# Industrial-Controller_3_3V_Domain.net
KiCad netlist of a schematic drawn in Altium Designer
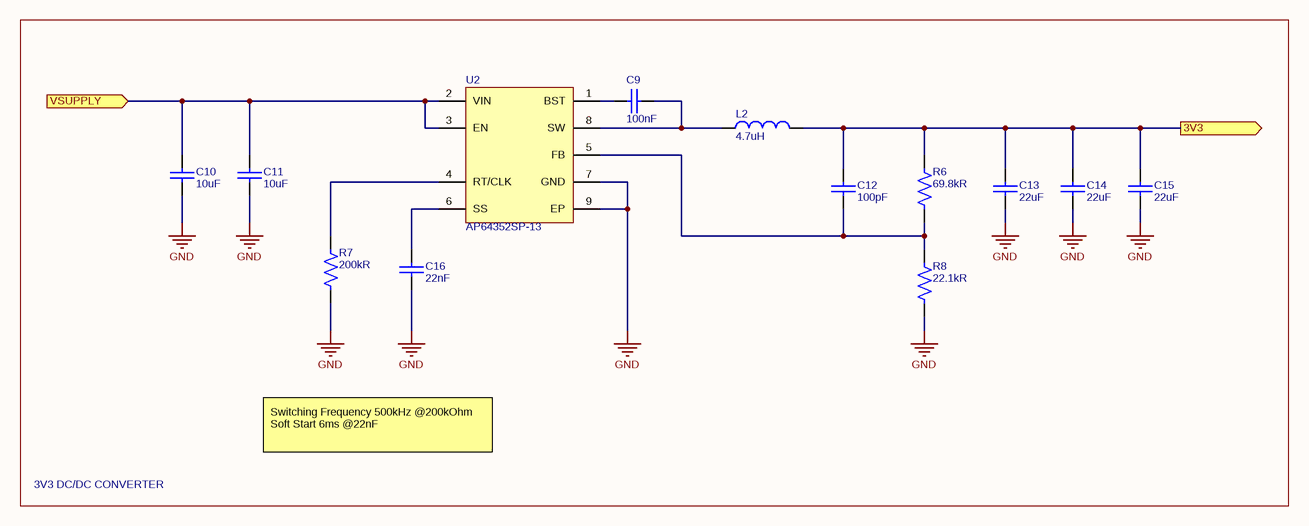
[diagram p0: Industrial-Controller_3.3V_Domain.SchDoc]

(export (version "E")
  (design (tool "Eeschema 10.0.6"))
  (components
    (comp (ref "C9")
      (value "100nF")
      (footprint "CAP_0603")
      (description "CAP CER 0.1UF 50V X7R 0603")
      (fields (field (name "TOLERANCE") "10%"))
      (libsource (lib "Door_Controller_Single") (part "CL10B104KB8NNNL"))
    )
    (comp (ref "C10")
      (value "10uF")
      (footprint "CAP_1210")
      (description "CAP CER 10UF 50V X7R 1210")
      (fields (field (name "TOLERANCE") "10%"))
      (libsource (lib "Door_Controller_Single") (part "CL32B106KBJNNWE"))
    )
    (comp (ref "C11")
      (value "10uF")
      (footprint "CAP_1210")
      (description "CAP CER 10UF 50V X7R 1210")
      (fields (field (name "TOLERANCE") "10%"))
      (libsource (lib "Door_Controller_Single") (part "CL32B106KBJNNWE"))
    )
    (comp (ref "C12")
      (value "100pF")
      (footprint "CAP_0603")
      (description "CAP CER 100PF 50V X7R 0603")
      (fields (field (name "TOLERANCE") "10%"))
      (libsource (lib "Door_Controller_Single") (part "CL10B101KB8NFNC"))
    )
    (comp (ref "C13")
      (value "22uF")
      (footprint "CAP_1210")
      (description "CAP CER 22UF 25V X7R 1210")
      (fields (field (name "TOLERANCE") "10%"))
      (libsource (lib "Door_Controller_Single") (part "CL32B226KAJNNNE"))
    )
    (comp (ref "C14")
      (value "22uF")
      (footprint "CAP_1210")
      (description "CAP CER 22UF 25V X7R 1210")
      (fields (field (name "TOLERANCE") "10%"))
      (libsource (lib "Door_Controller_Single") (part "CL32B226KAJNNNE"))
    )
    (comp (ref "C15")
      (value "22uF")
      (footprint "CAP_1210")
      (description "CAP CER 22UF 25V X7R 1210")
      (fields (field (name "TOLERANCE") "10%"))
      (libsource (lib "Door_Controller_Single") (part "CL32B226KAJNNNE"))
    )
    (comp (ref "C16")
      (value "22nF")
      (footprint "CAP_0603")
      (description "CAP CER 0.022UF 50V X7R 0603")
      (fields (field (name "TOLERANCE") "10%"))
      (libsource (lib "Door_Controller_Single") (part "CL10B223KB8WPNC"))
    )
    (comp (ref "L2")
      (value "4.7uH")
      (footprint "SRU1048")
      (description "FIXED IND 4.7UH 5.5A 9.5MOHM SMD")
      (fields (field (name "TOLERANCE") "30%"))
      (libsource (lib "Door_Controller_Single") (part "SRU1048-4R7Y"))
    )
    (comp (ref "R6")
      (value "69.8kR")
      (footprint "RES_0603")
      (description "RES 69.8K OHM 1% 1/10W 0603")
      (fields (field (name "TOLERANCE") "1%"))
      (libsource (lib "Door_Controller_Single") (part "RC0603FR-0769K8L"))
    )
    (comp (ref "R7")
      (value "200kR")
      (footprint "RES_0603")
      (description "RES 200K OHM 1% 1/10W 0603")
      (fields (field (name "TOLERANCE") "1%"))
      (libsource (lib "Door_Controller_Single") (part "RC0603FR-07200KL"))
    )
    (comp (ref "R8")
      (value "22.1kR")
      (footprint "RES_0603")
      (description "RES 22.1K OHM 1% 1/10W 0603")
      (fields (field (name "TOLERANCE") "1%"))
      (libsource (lib "Door_Controller_Single") (part "RC0603FR-0722K1L"))
    )
    (comp (ref "U2")
      (value "AP64352SP-13")
      (footprint "SOIC-8EP_150mil")
      (description "IC DCDC CONV BUCK 3.5A SO-8EP")
      (libsource (lib "Door_Controller_Single") (part "AP64352SP-13"))
    )
  )
  (nets
    (net (code "1") (name "/3V3") (class "Default")
      (node (ref "C12") (pin "2") (pinfunction "2_2") (pintype "passive"))
      (node (ref "C13") (pin "2") (pinfunction "2_2") (pintype "passive"))
      (node (ref "C14") (pin "2") (pinfunction "2_2") (pintype "passive"))
      (node (ref "C15") (pin "2") (pinfunction "2_2") (pintype "passive"))
      (node (ref "L2") (pin "2") (pinfunction "2_2") (pintype "passive"))
      (node (ref "R6") (pin "1") (pinfunction "1_1") (pintype "passive"))
    )
    (net (code "2") (name "/VSUPPLY") (class "Default")
      (node (ref "C10") (pin "2") (pinfunction "2_2") (pintype "passive"))
      (node (ref "C11") (pin "2") (pinfunction "2_2") (pintype "passive"))
      (node (ref "U2") (pin "2") (pinfunction "VIN_2") (pintype "passive"))
      (node (ref "U2") (pin "3") (pinfunction "EN_3") (pintype "passive"))
    )
    (net (code "3") (name "GND") (class "Default")
      (node (ref "C10") (pin "1") (pinfunction "1_1") (pintype "passive"))
      (node (ref "C11") (pin "1") (pinfunction "1_1") (pintype "passive"))
      (node (ref "C13") (pin "1") (pinfunction "1_1") (pintype "passive"))
      (node (ref "C14") (pin "1") (pinfunction "1_1") (pintype "passive"))
      (node (ref "C15") (pin "1") (pinfunction "1_1") (pintype "passive"))
      (node (ref "C16") (pin "1") (pinfunction "1_1") (pintype "passive"))
      (node (ref "R7") (pin "2") (pinfunction "2_2") (pintype "passive"))
      (node (ref "R8") (pin "2") (pinfunction "2_2") (pintype "passive"))
      (node (ref "U2") (pin "7") (pinfunction "GND_7") (pintype "passive"))
      (node (ref "U2") (pin "9") (pinfunction "EP_9") (pintype "passive"))
    )
    (net (code "4") (name "Net-(U2-BST)") (class "Default")
      (node (ref "C9") (pin "2") (pinfunction "2_2") (pintype "passive"))
      (node (ref "U2") (pin "1") (pinfunction "BST_1") (pintype "passive"))
    )
    (net (code "5") (name "Net-(U2-FB)") (class "Default")
      (node (ref "C12") (pin "1") (pinfunction "1_1") (pintype "passive"))
      (node (ref "R6") (pin "2") (pinfunction "2_2") (pintype "passive"))
      (node (ref "R8") (pin "1") (pinfunction "1_1") (pintype "passive"))
      (node (ref "U2") (pin "5") (pinfunction "FB_5") (pintype "passive"))
    )
    (net (code "6") (name "Net-(U2-RT{slash}CLK)") (class "Default")
      (node (ref "R7") (pin "1") (pinfunction "1_1") (pintype "passive"))
      (node (ref "U2") (pin "4") (pinfunction "RT/CLK_4") (pintype "passive"))
    )
    (net (code "7") (name "Net-(U2-SS)") (class "Default")
      (node (ref "C16") (pin "2") (pinfunction "2_2") (pintype "passive"))
      (node (ref "U2") (pin "6") (pinfunction "SS_6") (pintype "passive"))
    )
    (net (code "8") (name "Net-(U2-SW)") (class "Default")
      (node (ref "C9") (pin "1") (pinfunction "1_1") (pintype "passive"))
      (node (ref "L2") (pin "1") (pinfunction "1_1") (pintype "passive"))
      (node (ref "U2") (pin "8") (pinfunction "SW_8") (pintype "passive"))
    )
  )
)
